# ESP07_Tool.net
KiCad netlist of a schematic drawn in EAGLE
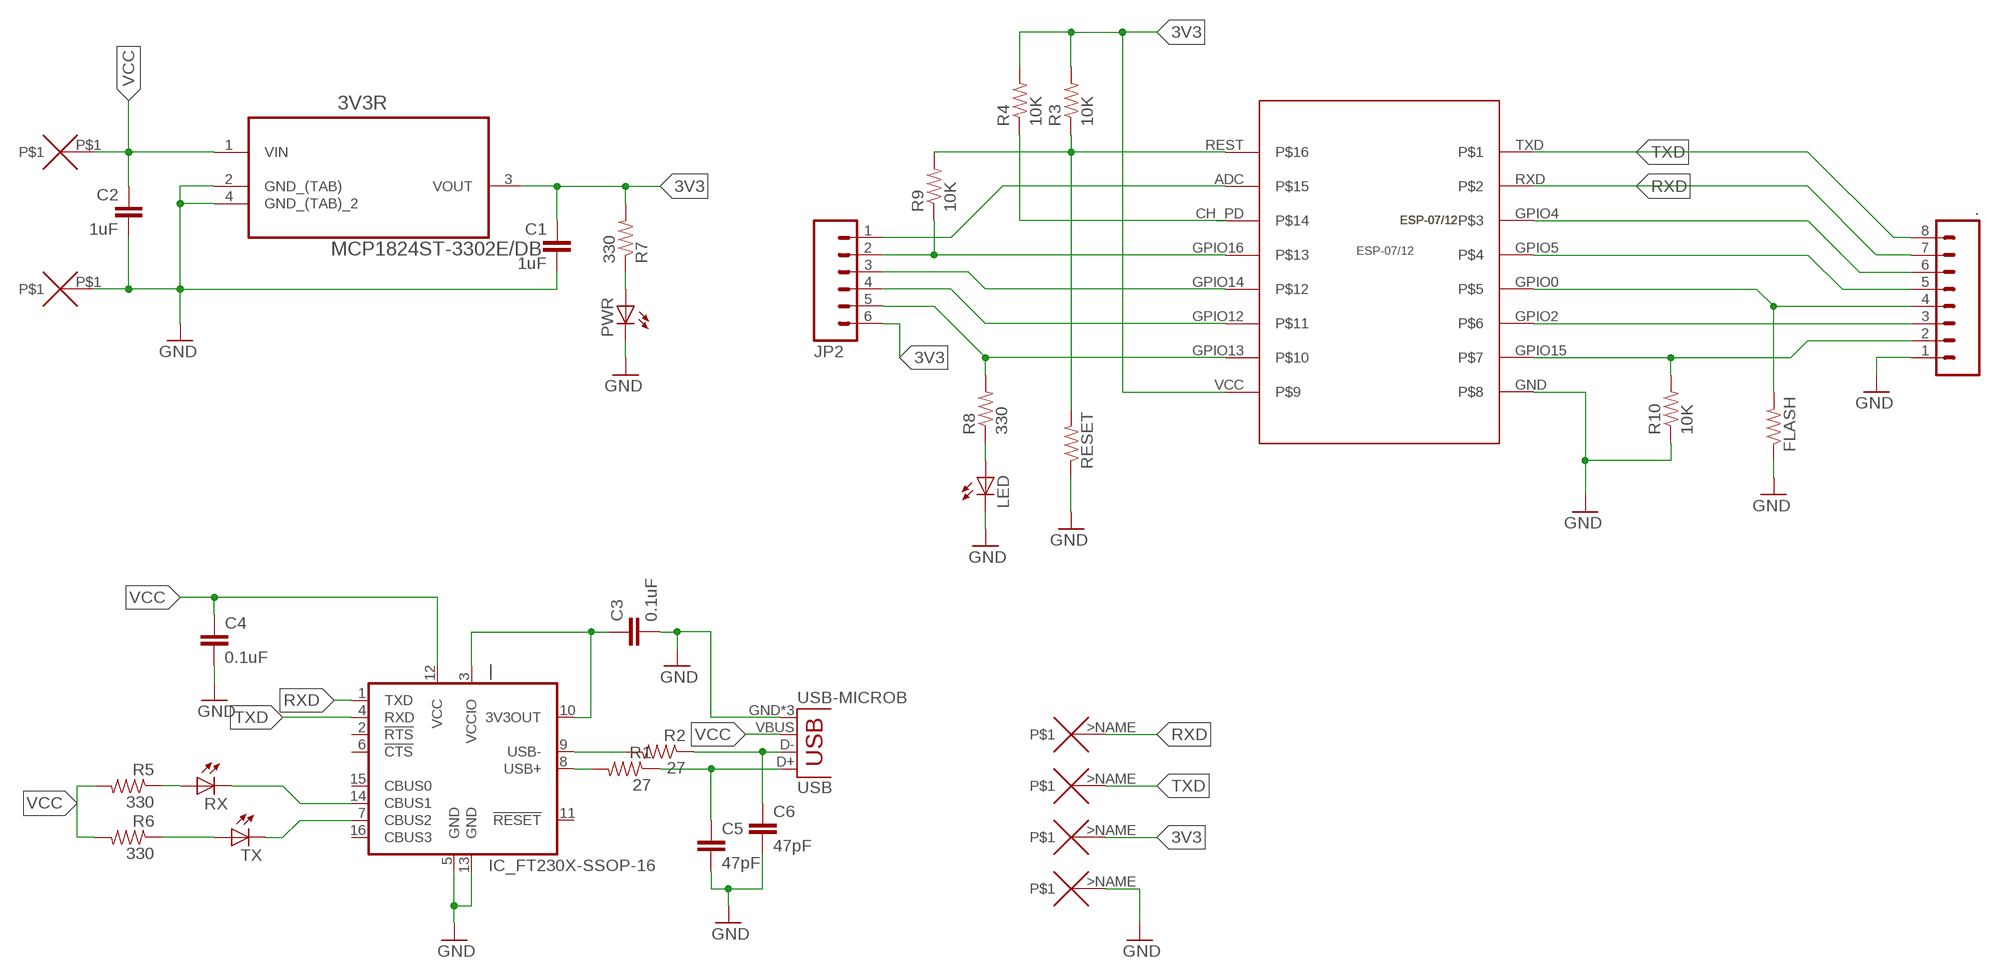
[diagram p0: schematic, sheet 1]

(export (version "E")
  (design (tool "Eeschema 10.0.6"))
  (components
    (comp (ref ".")
      (value "M08SILK_FEMALE_PTH")
      (footprint "eagle-import:1X08")
      (libsource (lib "eagle-import") (part "M08SILK_FEMALE_PTH"))
    )
    (comp (ref "3V3R")
      (value "MCP1824ST-3302E/DB")
      (footprint "eagle-import:SOT230P700X180-4N")
      (libsource (lib "eagle-import") (part "MCP1824ST-3302E/DB"))
    )
    (comp (ref "C1")
      (value "1uF")
      (footprint "eagle-import:0805-CAP")
      (libsource (lib "eagle-import") (part "CAP"))
    )
    (comp (ref "C2")
      (value "1uF")
      (footprint "eagle-import:0805-CAP")
      (libsource (lib "eagle-import") (part "CAP"))
    )
    (comp (ref "C3")
      (value "0.1uF")
      (footprint "eagle-import:0805-CAP")
      (libsource (lib "eagle-import") (part "CAP"))
    )
    (comp (ref "C4")
      (value "0.1uF")
      (footprint "eagle-import:0805-CAP")
      (libsource (lib "eagle-import") (part "CAP"))
    )
    (comp (ref "C5")
      (value "47pF")
      (footprint "eagle-import:0805-CAP")
      (libsource (lib "eagle-import") (part "CAP"))
    )
    (comp (ref "C6")
      (value "47pF")
      (footprint "eagle-import:0805-CAP")
      (libsource (lib "eagle-import") (part "CAP"))
    )
    (comp (ref "FLASH")
      (value "RESISTOR2010")
      (footprint "eagle-import:R2010")
      (libsource (lib "eagle-import") (part "RESISTOR2010"))
    )
    (comp (ref "JP2")
      (value "M06SILK_FEMALE_PTH")
      (footprint "eagle-import:1X06")
      (libsource (lib "eagle-import") (part "M06SILK_FEMALE_PTH"))
    )
    (comp (ref "LED")
      (value "LEDCHIPLED_0805")
      (footprint "eagle-import:CHIPLED_0805")
      (libsource (lib "eagle-import") (part "LEDCHIPLED_0805"))
    )
    (comp (ref "PWR")
      (value "LEDCHIPLED_0805")
      (footprint "eagle-import:CHIPLED_0805")
      (libsource (lib "eagle-import") (part "LEDCHIPLED_0805"))
    )
    (comp (ref "R1")
      (value "27")
      (footprint "eagle-import:0805")
      (libsource (lib "eagle-import") (part "RESISTOR0805-RES"))
    )
    (comp (ref "R2")
      (value "27")
      (footprint "eagle-import:0805")
      (libsource (lib "eagle-import") (part "RESISTOR0805-RES"))
    )
    (comp (ref "R3")
      (value "10K")
      (footprint "eagle-import:0805")
      (libsource (lib "eagle-import") (part "RESISTOR0805-RES"))
    )
    (comp (ref "R4")
      (value "10K")
      (footprint "eagle-import:0805")
      (libsource (lib "eagle-import") (part "RESISTOR0805-RES"))
    )
    (comp (ref "R5")
      (value "330")
      (footprint "eagle-import:0805")
      (libsource (lib "eagle-import") (part "RESISTOR0805-RES"))
    )
    (comp (ref "R6")
      (value "330")
      (footprint "eagle-import:0805")
      (libsource (lib "eagle-import") (part "RESISTOR0805-RES"))
    )
    (comp (ref "R7")
      (value "330")
      (footprint "eagle-import:0805")
      (libsource (lib "eagle-import") (part "RESISTOR0805-RES"))
    )
    (comp (ref "R8")
      (value "330")
      (footprint "eagle-import:0805")
      (libsource (lib "eagle-import") (part "RESISTOR0805-RES"))
    )
    (comp (ref "R9")
      (value "10K")
      (footprint "eagle-import:0805")
      (libsource (lib "eagle-import") (part "RESISTOR0805-RES"))
    )
    (comp (ref "R10")
      (value "10K")
      (footprint "eagle-import:0805")
      (libsource (lib "eagle-import") (part "RESISTOR0805-RES"))
    )
    (comp (ref "RESET")
      (value "RESISTOR2010")
      (footprint "eagle-import:R2010")
      (libsource (lib "eagle-import") (part "RESISTOR2010"))
    )
    (comp (ref "RX")
      (value "LEDCHIPLED_0805")
      (footprint "eagle-import:CHIPLED_0805")
      (libsource (lib "eagle-import") (part "LEDCHIPLED_0805"))
    )
    (comp (ref "TX")
      (value "LEDCHIPLED_0805")
      (footprint "eagle-import:CHIPLED_0805")
      (libsource (lib "eagle-import") (part "LEDCHIPLED_0805"))
    )
    (comp (ref "U$1")
      (value "ESP-07/12")
      (footprint "eagle-import:ESP-07_12")
      (libsource (lib "eagle-import") (part "ESP-07/12"))
    )
    (comp (ref "U$2")
      (value "SMD-PAD-SM")
      (footprint "eagle-import:SMD-PAD3")
      (libsource (lib "eagle-import") (part "SMD-PAD-SM"))
    )
    (comp (ref "U$3")
      (value "SMD-PAD-SM")
      (footprint "eagle-import:SMD-PAD3")
      (libsource (lib "eagle-import") (part "SMD-PAD-SM"))
    )
    (comp (ref "U$4")
      (value "SMD-PAD1")
      (footprint "eagle-import:SMD-PAD1")
      (libsource (lib "eagle-import") (part "SMD-PAD1"))
    )
    (comp (ref "U$5")
      (value "SMD-PAD1")
      (footprint "eagle-import:SMD-PAD1")
      (libsource (lib "eagle-import") (part "SMD-PAD1"))
    )
    (comp (ref "U$6")
      (value "SMD-PAD1")
      (footprint "eagle-import:SMD-PAD1")
      (libsource (lib "eagle-import") (part "SMD-PAD1"))
    )
    (comp (ref "U$7")
      (value "SMD-PAD1")
      (footprint "eagle-import:SMD-PAD1")
      (libsource (lib "eagle-import") (part "SMD-PAD1"))
    )
    (comp (ref "USB")
      (value "USB-MICROB")
      (footprint "eagle-import:USB-MICROB")
      (libsource (lib "eagle-import") (part "USB-MICROB"))
    )
    (comp (ref "|")
      (value "IC_FT230X-SSOP-16")
      (footprint "eagle-import:SSOP-16-FTDI")
      (libsource (lib "eagle-import") (part "IC_FT230X-SSOP-16"))
    )
  )
  (nets
    (net (code "1") (name "3V3") (class "Default")
      (node (ref "3V3R") (pin "3") (pinfunction "VOUT_3") (pintype "output"))
      (node (ref "C1") (pin "1") (pinfunction "1_1") (pintype "passive"))
      (node (ref "JP2") (pin "6") (pinfunction "6_6") (pintype "passive"))
      (node (ref "R3") (pin "2") (pinfunction "2_2") (pintype "passive"))
      (node (ref "R4") (pin "2") (pinfunction "2_2") (pintype "passive"))
      (node (ref "R7") (pin "2") (pinfunction "2_2") (pintype "passive"))
      (node (ref "U$1") (pin "VCC") (pinfunction "P$9_VCC") (pintype "bidirectional"))
      (node (ref "U$6") (pin ">NAME") (pinfunction "P$1_>NAME") (pintype "bidirectional"))
    )
    (net (code "2") (name "GND") (class "Default")
      (node (ref ".") (pin "1") (pinfunction "1_1") (pintype "passive"))
      (node (ref "3V3R") (pin "2") (pinfunction "GND_(TAB)_2") (pintype "passive"))
      (node (ref "3V3R") (pin "4") (pinfunction "GND_(TAB)_2_4") (pintype "passive"))
      (node (ref "C1") (pin "2") (pinfunction "2_2") (pintype "passive"))
      (node (ref "C2") (pin "2") (pinfunction "2_2") (pintype "passive"))
      (node (ref "C3") (pin "2") (pinfunction "2_2") (pintype "passive"))
      (node (ref "C4") (pin "2") (pinfunction "2_2") (pintype "passive"))
      (node (ref "C5") (pin "2") (pinfunction "2_2") (pintype "passive"))
      (node (ref "C6") (pin "2") (pinfunction "2_2") (pintype "passive"))
      (node (ref "FLASH") (pin "1") (pinfunction "1_1") (pintype "passive"))
      (node (ref "LED") (pin "C") (pinfunction "C_C") (pintype "passive"))
      (node (ref "PWR") (pin "C") (pinfunction "C_C") (pintype "passive"))
      (node (ref "R10") (pin "1") (pinfunction "1_1") (pintype "passive"))
      (node (ref "RESET") (pin "1") (pinfunction "1_1") (pintype "passive"))
      (node (ref "U$1") (pin "GND") (pinfunction "P$8_GND") (pintype "bidirectional"))
      (node (ref "U$2") (pin "P$1") (pinfunction "P$1_P$1") (pintype "bidirectional"))
      (node (ref "U$7") (pin ">NAME") (pinfunction "P$1_>NAME") (pintype "bidirectional"))
      (node (ref "USB") (pin "GND") (pinfunction "GND_GND") (pintype "bidirectional"))
      (node (ref "USB") (pin "MT1") (pinfunction "GND_MT1") (pintype "bidirectional"))
      (node (ref "USB") (pin "MT2") (pinfunction "GND_MT2") (pintype "bidirectional"))
      (node (ref "|") (pin "13") (pinfunction "GND_13") (pintype "power_in"))
      (node (ref "|") (pin "5") (pinfunction "GND_5") (pintype "power_in"))
    )
    (net (code "3") (name "Net-(C5-Pad1)") (class "Default")
      (node (ref "C5") (pin "1") (pinfunction "1_1") (pintype "passive"))
      (node (ref "R1") (pin "1") (pinfunction "1_1") (pintype "passive"))
      (node (ref "USB") (pin "D+") (pinfunction "D+_D+") (pintype "bidirectional"))
    )
    (net (code "4") (name "Net-(C6-Pad1)") (class "Default")
      (node (ref "C6") (pin "1") (pinfunction "1_1") (pintype "passive"))
      (node (ref "R2") (pin "1") (pinfunction "1_1") (pintype "passive"))
      (node (ref "USB") (pin "D-") (pinfunction "D-_D-") (pintype "bidirectional"))
    )
    (net (code "5") (name "Net-(LED-PadA)") (class "Default")
      (node (ref "LED") (pin "A") (pinfunction "A_A") (pintype "passive"))
      (node (ref "R8") (pin "1") (pinfunction "1_1") (pintype "passive"))
    )
    (net (code "6") (name "Net-(PWR-PadA)") (class "Default")
      (node (ref "PWR") (pin "A") (pinfunction "A_A") (pintype "passive"))
      (node (ref "R7") (pin "1") (pinfunction "1_1") (pintype "passive"))
    )
    (net (code "7") (name "Net-(R5-Pad1)") (class "Default")
      (node (ref "R5") (pin "1") (pinfunction "1_1") (pintype "passive"))
      (node (ref "RX") (pin "A") (pinfunction "A_A") (pintype "passive"))
    )
    (net (code "8") (name "Net-(R6-Pad1)") (class "Default")
      (node (ref "R6") (pin "1") (pinfunction "1_1") (pintype "passive"))
      (node (ref "TX") (pin "A") (pinfunction "A_A") (pintype "passive"))
    )
    (net (code "9") (name "Net-(U$1-P$3)") (class "Default")
      (node (ref ".") (pin "6") (pinfunction "6_6") (pintype "passive"))
      (node (ref "U$1") (pin "GPIO4") (pinfunction "P$3_GPIO4") (pintype "bidirectional"))
    )
    (net (code "10") (name "Net-(U$1-P$4)") (class "Default")
      (node (ref ".") (pin "5") (pinfunction "5_5") (pintype "passive"))
      (node (ref "U$1") (pin "GPIO5") (pinfunction "P$4_GPIO5") (pintype "bidirectional"))
    )
    (net (code "11") (name "Net-(U$1-P$5)") (class "Default")
      (node (ref ".") (pin "4") (pinfunction "4_4") (pintype "passive"))
      (node (ref "FLASH") (pin "2") (pinfunction "2_2") (pintype "passive"))
      (node (ref "U$1") (pin "GPIO0") (pinfunction "P$5_GPIO0") (pintype "bidirectional"))
    )
    (net (code "12") (name "Net-(U$1-P$6)") (class "Default")
      (node (ref ".") (pin "3") (pinfunction "3_3") (pintype "passive"))
      (node (ref "U$1") (pin "GPIO2") (pinfunction "P$6_GPIO2") (pintype "bidirectional"))
    )
    (net (code "13") (name "Net-(U$1-P$7)") (class "Default")
      (node (ref ".") (pin "2") (pinfunction "2_2") (pintype "passive"))
      (node (ref "R10") (pin "2") (pinfunction "2_2") (pintype "passive"))
      (node (ref "U$1") (pin "GPIO15") (pinfunction "P$7_GPIO15") (pintype "bidirectional"))
    )
    (net (code "14") (name "Net-(U$1-P$10)") (class "Default")
      (node (ref "JP2") (pin "5") (pinfunction "5_5") (pintype "passive"))
      (node (ref "R8") (pin "2") (pinfunction "2_2") (pintype "passive"))
      (node (ref "U$1") (pin "GPIO13") (pinfunction "P$10_GPIO13") (pintype "bidirectional"))
    )
    (net (code "15") (name "Net-(U$1-P$11)") (class "Default")
      (node (ref "JP2") (pin "4") (pinfunction "4_4") (pintype "passive"))
      (node (ref "U$1") (pin "GPIO12") (pinfunction "P$11_GPIO12") (pintype "bidirectional"))
    )
    (net (code "16") (name "Net-(U$1-P$12)") (class "Default")
      (node (ref "JP2") (pin "3") (pinfunction "3_3") (pintype "passive"))
      (node (ref "U$1") (pin "GPIO14") (pinfunction "P$12_GPIO14") (pintype "bidirectional"))
    )
    (net (code "17") (name "Net-(U$1-P$13)") (class "Default")
      (node (ref "JP2") (pin "2") (pinfunction "2_2") (pintype "passive"))
      (node (ref "R9") (pin "1") (pinfunction "1_1") (pintype "passive"))
      (node (ref "U$1") (pin "GPIO16") (pinfunction "P$13_GPIO16") (pintype "bidirectional"))
    )
    (net (code "18") (name "Net-(U$1-P$14)") (class "Default")
      (node (ref "R4") (pin "1") (pinfunction "1_1") (pintype "passive"))
      (node (ref "U$1") (pin "CH_PD") (pinfunction "P$14_CH_PD") (pintype "bidirectional"))
    )
    (net (code "19") (name "Net-(U$1-P$15)") (class "Default")
      (node (ref "JP2") (pin "1") (pinfunction "1_1") (pintype "passive"))
      (node (ref "U$1") (pin "ADC") (pinfunction "P$15_ADC") (pintype "bidirectional"))
    )
    (net (code "20") (name "Net-(U$1-P$16)") (class "Default")
      (node (ref "R3") (pin "1") (pinfunction "1_1") (pintype "passive"))
      (node (ref "R9") (pin "2") (pinfunction "2_2") (pintype "passive"))
      (node (ref "RESET") (pin "2") (pinfunction "2_2") (pintype "passive"))
      (node (ref "U$1") (pin "REST") (pinfunction "P$16_REST") (pintype "bidirectional"))
    )
    (net (code "21") (name "Net-(|-3V3OUT)") (class "Default")
      (node (ref "C3") (pin "1") (pinfunction "1_1") (pintype "passive"))
      (node (ref "|") (pin "10") (pinfunction "3V3OUT_10") (pintype "power_in"))
      (node (ref "|") (pin "3") (pinfunction "VCCIO_3") (pintype "power_in"))
    )
    (net (code "22") (name "Net-(|-CBUS1)") (class "Default")
      (node (ref "RX") (pin "C") (pinfunction "C_C") (pintype "passive"))
      (node (ref "|") (pin "14") (pinfunction "CBUS1_14") (pintype "bidirectional"))
    )
    (net (code "23") (name "Net-(|-CBUS2)") (class "Default")
      (node (ref "TX") (pin "C") (pinfunction "C_C") (pintype "passive"))
      (node (ref "|") (pin "7") (pinfunction "CBUS2_7") (pintype "bidirectional"))
    )
    (net (code "24") (name "Net-(|-USB+)") (class "Default")
      (node (ref "R1") (pin "2") (pinfunction "2_2") (pintype "passive"))
      (node (ref "|") (pin "8") (pinfunction "USB+_8") (pintype "output"))
    )
    (net (code "25") (name "Net-(|-USB-)") (class "Default")
      (node (ref "R2") (pin "2") (pinfunction "2_2") (pintype "passive"))
      (node (ref "|") (pin "9") (pinfunction "USB-_9") (pintype "input"))
    )
    (net (code "26") (name "RXD") (class "Default")
      (node (ref ".") (pin "7") (pinfunction "7_7") (pintype "passive"))
      (node (ref "U$1") (pin "RXD") (pinfunction "P$2_RXD") (pintype "bidirectional"))
      (node (ref "U$4") (pin ">NAME") (pinfunction "P$1_>NAME") (pintype "bidirectional"))
      (node (ref "|") (pin "1") (pinfunction "TXD_1") (pintype "output"))
    )
    (net (code "27") (name "TXD") (class "Default")
      (node (ref ".") (pin "8") (pinfunction "8_8") (pintype "passive"))
      (node (ref "U$1") (pin "TXD") (pinfunction "P$1_TXD") (pintype "bidirectional"))
      (node (ref "U$5") (pin ">NAME") (pinfunction "P$1_>NAME") (pintype "bidirectional"))
      (node (ref "|") (pin "4") (pinfunction "RXD_4") (pintype "input"))
    )
    (net (code "28") (name "VCC") (class "Default")
      (node (ref "3V3R") (pin "1") (pinfunction "VIN_1") (pintype "input"))
      (node (ref "C2") (pin "1") (pinfunction "1_1") (pintype "passive"))
      (node (ref "C4") (pin "1") (pinfunction "1_1") (pintype "passive"))
      (node (ref "R5") (pin "2") (pinfunction "2_2") (pintype "passive"))
      (node (ref "R6") (pin "2") (pinfunction "2_2") (pintype "passive"))
      (node (ref "U$3") (pin "P$1") (pinfunction "P$1_P$1") (pintype "bidirectional"))
      (node (ref "USB") (pin "VBUS") (pinfunction "VBUS_VBUS") (pintype "bidirectional"))
      (node (ref "|") (pin "12") (pinfunction "VCC_12") (pintype "power_in"))
    )
    (net (code "29") (name "unconnected-(|-CBUS0-Pad15)") (class "Default")
      (node (ref "|") (pin "15") (pinfunction "CBUS0_15") (pintype "bidirectional"))
    )
    (net (code "30") (name "unconnected-(|-CBUS3-Pad16)") (class "Default")
      (node (ref "|") (pin "16") (pinfunction "CBUS3_16") (pintype "bidirectional"))
    )
    (net (code "31") (name "unconnected-(|-~{CTS}-Pad6)") (class "Default")
      (node (ref "|") (pin "6") (pinfunction "~{CTS}_6") (pintype "bidirectional"))
    )
    (net (code "32") (name "unconnected-(|-~{RESET}-Pad11)") (class "Default")
      (node (ref "|") (pin "11") (pinfunction "~{RESET}_11") (pintype "bidirectional"))
    )
    (net (code "33") (name "unconnected-(|-~{RTS}-Pad2)") (class "Default")
      (node (ref "|") (pin "2") (pinfunction "~{RTS}_2") (pintype "bidirectional"))
    )
  )
)
